# Sheet1.net
KiCad netlist of a schematic drawn in Altium Designer
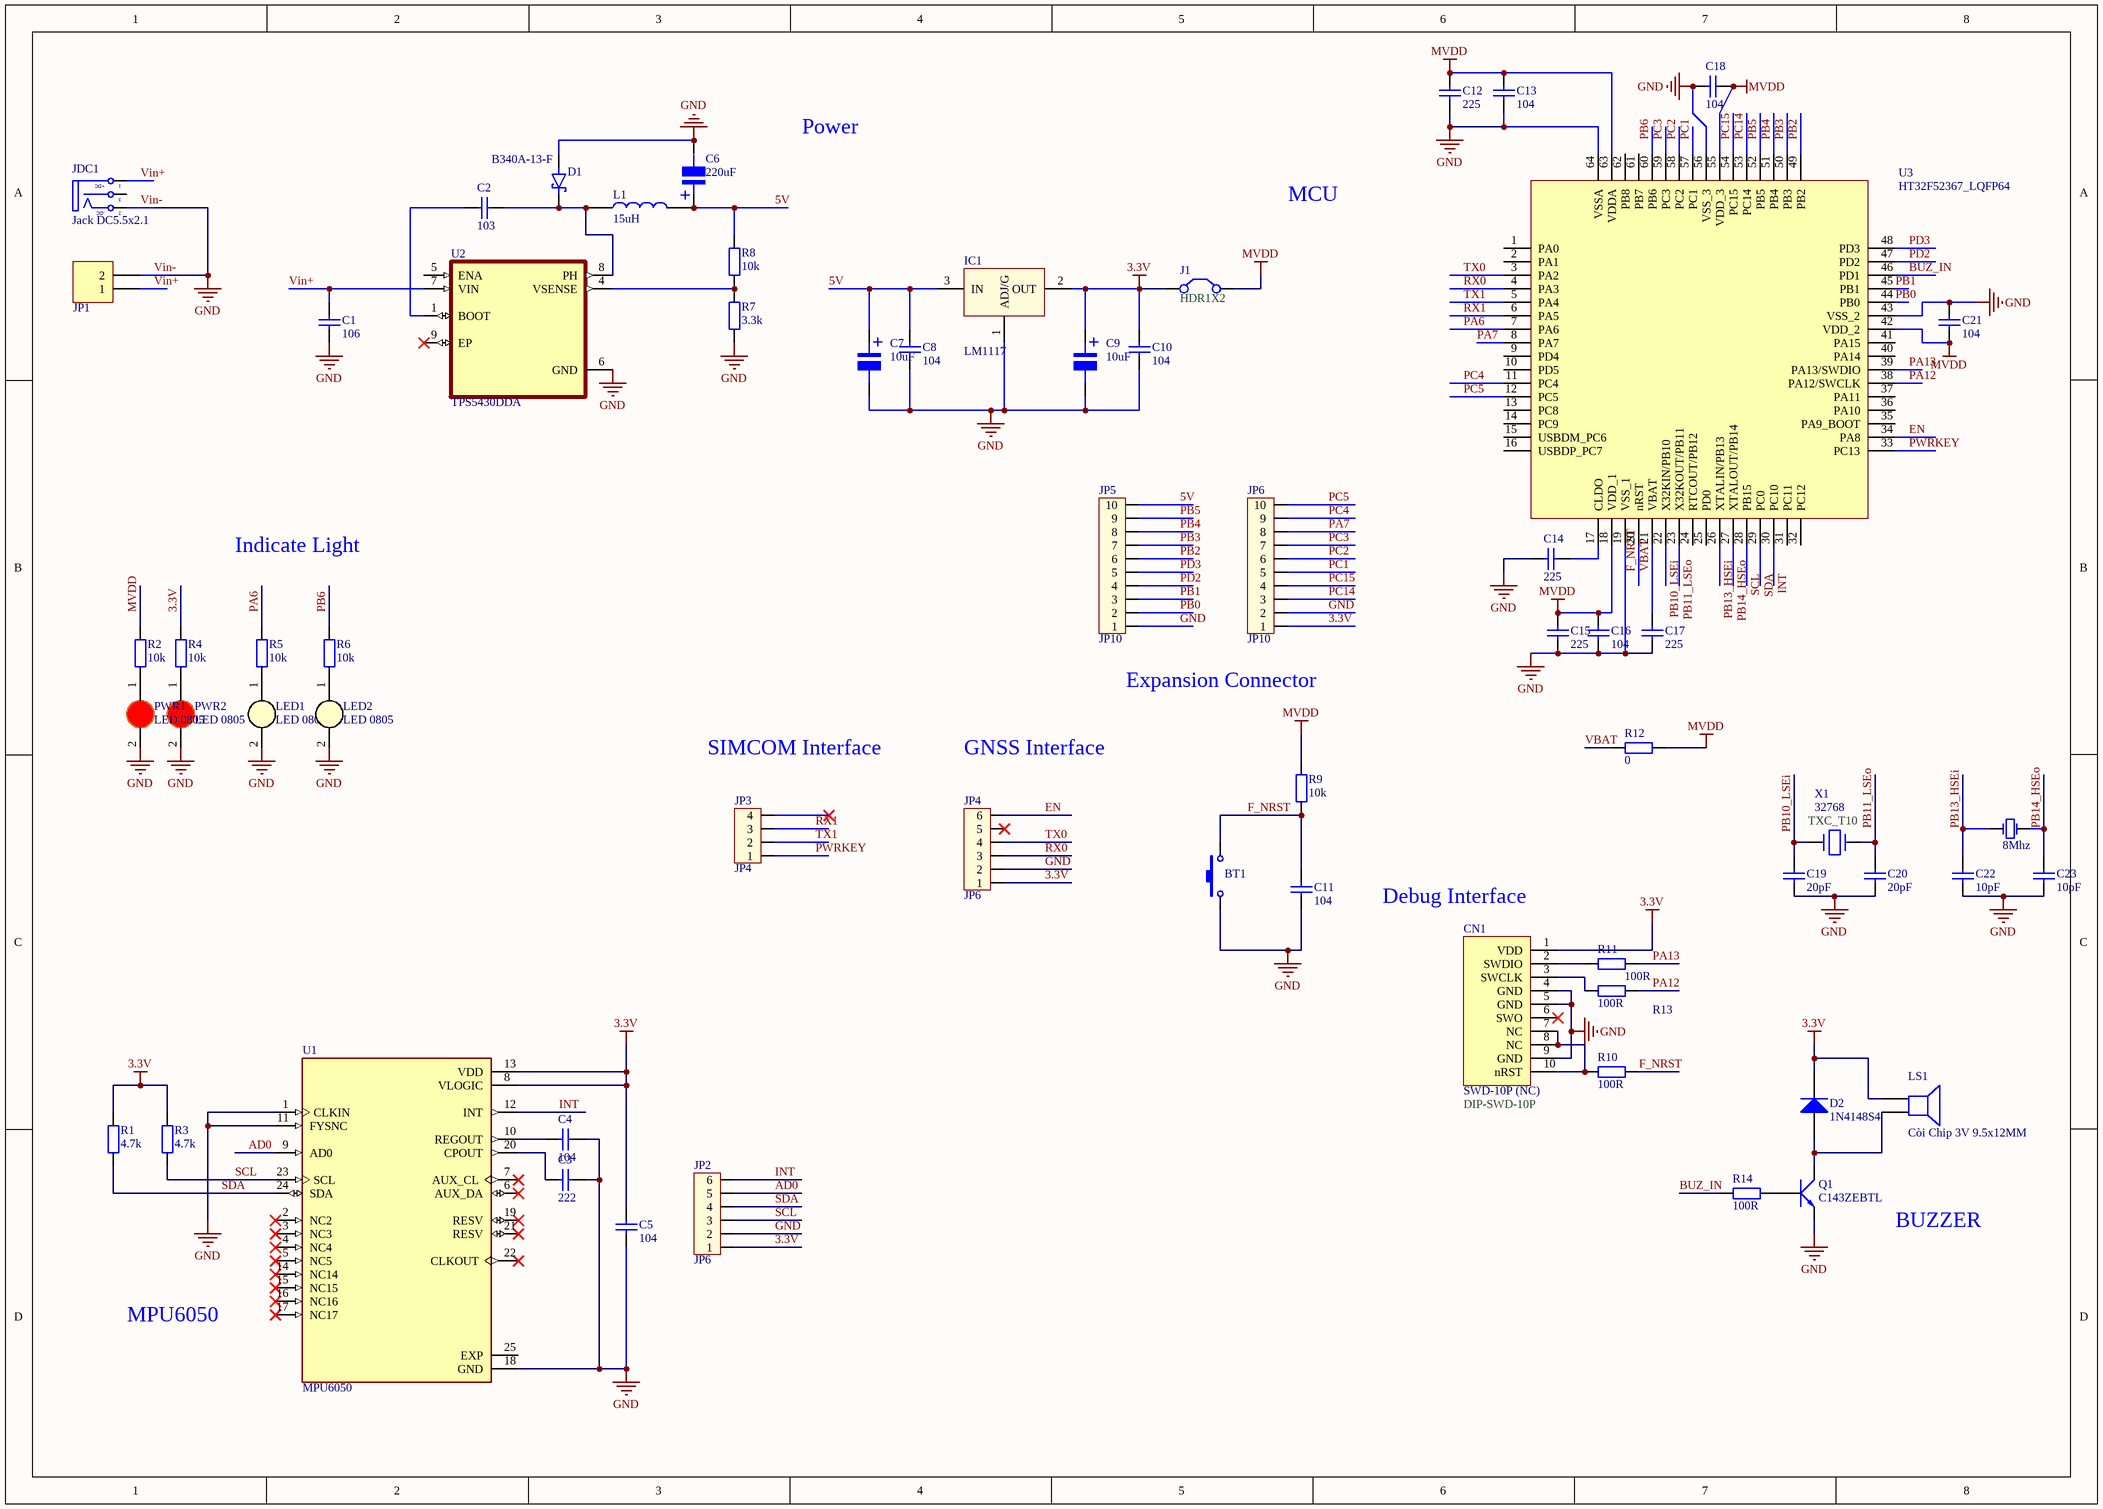
[diagram p0: Sheet1.SchDoc]

(export (version "E")
  (design (tool "Eeschema 10.0.6"))
  (components
    (comp (ref "BT1")
      (value "Nut Nhan 2 Chan SMD 3x6x2.5")
      (footprint "Nut Nhan 2 Chan SMD 3x6x2.5")
      (libsource (lib "Altium_Lib_by_KhueNguyenCreator") (part "Nut Nhan 2 Chan SMD 3x6x2.5"))
    )
    (comp (ref "C1")
      (value "106")
      (footprint "Tu 0805")
      (description "Dán")
      (libsource (lib "THU VIEN SCH") (part "Tu 0805 106 16V 10%"))
    )
    (comp (ref "C2")
      (value "103")
      (footprint "tu 0805")
      (description "Dán")
      (libsource (lib "THU VIEN SCH") (part "Tu 0805 104 50V 10%"))
    )
    (comp (ref "C3")
      (value "222")
      (footprint "tu 0805")
      (description "Dán")
      (libsource (lib "THU VIEN SCH") (part "Tu 0805 222 50V 10%"))
    )
    (comp (ref "C4")
      (value "104")
      (footprint "tu 0603")
      (description "Dán")
      (libsource (lib "THU VIEN SCH") (part "Tu 0603 104 50V 10%"))
    )
    (comp (ref "C5")
      (value "104")
      (footprint "tu 0603")
      (description "Dán")
      (libsource (lib "THU VIEN SCH") (part "Tu 0603 104 50V 10%"))
    )
    (comp (ref "C6")
      (value "220uF")
      (footprint "tu nhom 8 (e)")
      (description "Dán")
      (libsource (lib "THU VIEN SCH") (part "Tu Nhom 220uF 10V"))
    )
    (comp (ref "C7")
      (value "10uF")
      (footprint "tu nhom 4 (b)")
      (description "Dán")
      (libsource (lib "THU VIEN SCH") (part "Tu Nhom 10uF 16V"))
    )
    (comp (ref "C8")
      (value "104")
      (footprint "tu 0805")
      (description "Dán")
      (libsource (lib "THU VIEN SCH") (part "Tu 0805 104 50V 10%"))
    )
    (comp (ref "C9")
      (value "10uF")
      (footprint "tu nhom 4 (b)")
      (description "Dán")
      (libsource (lib "THU VIEN SCH") (part "Tu Nhom 10uF 16V"))
    )
    (comp (ref "C10")
      (value "104")
      (footprint "tu 0805")
      (description "Dán")
      (libsource (lib "THU VIEN SCH") (part "Tu 0805 104 50V 10%"))
    )
    (comp (ref "C11")
      (value "104")
      (footprint "tu 0603")
      (description "Dán")
      (libsource (lib "THU VIEN SCH") (part "Tu 0603 104 50V 10%"))
    )
    (comp (ref "C12")
      (value "225")
      (footprint "tu 0805")
      (description "Dán")
      (libsource (lib "THU VIEN SCH") (part "Tu 0805 225 25V 10%"))
    )
    (comp (ref "C13")
      (value "104")
      (footprint "tu 0603")
      (description "Dán")
      (libsource (lib "THU VIEN SCH") (part "Tu 0603 104 50V 10%"))
    )
    (comp (ref "C14")
      (value "225")
      (footprint "tu 0805")
      (description "Dán")
      (libsource (lib "THU VIEN SCH") (part "Tu 0805 225 25V 10%"))
    )
    (comp (ref "C15")
      (value "225")
      (footprint "tu 0805")
      (description "Dán")
      (libsource (lib "THU VIEN SCH") (part "Tu 0805 225 25V 10%"))
    )
    (comp (ref "C16")
      (value "104")
      (footprint "tu 0603")
      (description "Dán")
      (libsource (lib "THU VIEN SCH") (part "Tu 0603 104 50V 10%"))
    )
    (comp (ref "C17")
      (value "225")
      (footprint "tu 0805")
      (description "Dán")
      (libsource (lib "THU VIEN SCH") (part "Tu 0805 225 25V 10%"))
    )
    (comp (ref "C18")
      (value "104")
      (footprint "tu 0603")
      (description "Dán")
      (libsource (lib "THU VIEN SCH") (part "Tu 0603 104 50V 10%"))
    )
    (comp (ref "C19")
      (value "20pF")
      (footprint "tu 0805")
      (description "Dán")
      (libsource (lib "THU VIEN SCH") (part "Tu 0805 20pF 50V 10%"))
    )
    (comp (ref "C20")
      (value "20pF")
      (footprint "tu 0805")
      (description "Dán")
      (libsource (lib "THU VIEN SCH") (part "Tu 0805 20pF 50V 10%"))
    )
    (comp (ref "C21")
      (value "104")
      (footprint "tu 0603")
      (description "Dán")
      (libsource (lib "THU VIEN SCH") (part "Tu 0603 104 50V 10%"))
    )
    (comp (ref "C22")
      (value "10pF")
      (footprint "tu 0603")
      (description "Dán")
      (libsource (lib "THU VIEN SCH") (part "Tu 0603 104 50V 10%"))
    )
    (comp (ref "C23")
      (value "10pF")
      (footprint "tu 0603")
      (description "Dán")
      (libsource (lib "THU VIEN SCH") (part "Tu 0603 104 50V 10%"))
    )
    (comp (ref "CN1")
      (value "SWD-10P (NC)")
      (footprint "DIP-SWD-10P-2")
      (description "SWD Connector")
      (fields (field (name "PACKAGE") "DIP-SWD-10P"))
      (libsource (lib "HT32F12345_SK") (part "DIP-SWD-10P"))
    )
    (comp (ref "D1")
      (value "B340A-13-F")
      (footprint "DIOM5226X240N")
      (description "Diode Schottky 40V 3A Surface Mount SMA")
      (fields (field (name "MF") "Diodes Inc."))
      (libsource (lib "B340A-13-F") (part "B340A-13-F"))
    )
    (comp (ref "D2")
      (value "1N4148S4")
      (footprint "DIODE SOD-123")
      (description "Dán")
      (libsource (lib "Altium_Lib_by_KhueNguyenCreator") (part "Diode S4"))
    )
    (comp (ref "IC1")
      (value "LM1117")
      (footprint "SOT223-4N")
      (description "Available in 1.8V, 2.5V, 2.85V, 3.3V, 5V, and  Adjustable Versions")
      (libsource (lib "syhaunguyen") (part "LM1117"))
    )
    (comp (ref "J1")
      (value "Jumper")
      (footprint "HDR1X2")
      (description "Jumper Wire")
      (fields (field (name "PACKAGE") "HDR1X2"))
      (libsource (lib "HT32F52367_ESK32-30510") (part "Jumper"))
    )
    (comp (ref "JDC1")
      (value "Jack DC5.5x2.1")
      (footprint "DC-IN")
      (description "Cắm")
      (libsource (lib "THU VIEN SCH") (part "Jac_DC"))
    )
    (comp (ref "JP1")
      (value "Header 2_1")
      (footprint "HED2")
      (description "Header, 2-Pin")
      (fields (field (name "MANUFACTURER") "Generic Components"))
      (libsource (lib "syhaunguyen") (part "Header 2_1"))
    )
    (comp (ref "JP2")
      (value "JP6")
      (footprint "CON6")
      (description "Connector 6")
      (libsource (lib "syhaunguyen") (part "Con6"))
    )
    (comp (ref "JP3")
      (value "JP4")
      (footprint "CON4")
      (description "Connector 4")
      (libsource (lib "syhaunguyen") (part "Con4"))
    )
    (comp (ref "JP4")
      (value "JP6")
      (footprint "CON6")
      (description "Connector 6")
      (libsource (lib "syhaunguyen") (part "Con6"))
    )
    (comp (ref "JP5")
      (value "JP10")
      (footprint "CON10")
      (description "Connector 10")
      (libsource (lib "syhaunguyen") (part "Con10"))
    )
    (comp (ref "JP6")
      (value "JP10")
      (footprint "CON10")
      (description "Connector 10")
      (libsource (lib "syhaunguyen") (part "Con10"))
    )
    (comp (ref "L1")
      (value "15uH")
      (footprint "Cuon Cam 7x7x5")
      (description "Dán")
      (libsource (lib "Cuon Cam") (part "CUON CAM 47uH SMD"))
    )
    (comp (ref "LED1")
      (value "LED 0805")
      (footprint "led 0805")
      (description "Dán")
      (libsource (lib "Altium_Lib_by_KhueNguyenCreator") (part "LED 0805 Trang"))
    )
    (comp (ref "LED2")
      (value "LED 0805")
      (footprint "led 0805")
      (description "Dán")
      (libsource (lib "Altium_Lib_by_KhueNguyenCreator") (part "LED 0805 Trang"))
    )
    (comp (ref "LS1")
      (value "Còi Chip 3V 9.5x12MM")
      (footprint "SPEAKER")
      (description "Cắm")
      (libsource (lib "THU VIEN SCH") (part "Coi Chip 5V"))
    )
    (comp (ref "PWR1")
      (value "LED 0805")
      (footprint "led 0805")
      (description "Dán")
      (libsource (lib "Altium_Lib_by_KhueNguyenCreator") (part "LED 0805 Do"))
    )
    (comp (ref "PWR2")
      (value "LED 0805")
      (footprint "led 0805")
      (description "Dán")
      (libsource (lib "Altium_Lib_by_KhueNguyenCreator") (part "LED 0805 Do"))
    )
    (comp (ref "Q1")
      (value "C143ZEBTL")
      (footprint "SOT23")
      (description "NPN transistor")
      (libsource (lib "Altium_Lib_by_KhueNguyenCreator") (part "C1815 HF SMD"))
    )
    (comp (ref "R1")
      (value "4.7k")
      (footprint "tro smd 0805")
      (description "Dán")
      (libsource (lib "THU VIEN SCH") (part "Tro 0805 5% 4.7k"))
    )
    (comp (ref "R2")
      (value "10k")
      (footprint "TRO SMD 0603")
      (description "Dán")
      (libsource (lib "Altium_Lib_by_KhueNguyenCreator") (part "Tro 0603 1% 10k"))
    )
    (comp (ref "R3")
      (value "4.7k")
      (footprint "tro smd 0805")
      (description "Dán")
      (libsource (lib "THU VIEN SCH") (part "Tro 0805 5% 4.7k"))
    )
    (comp (ref "R4")
      (value "10k")
      (footprint "TRO SMD 0603")
      (description "Dán")
      (libsource (lib "Altium_Lib_by_KhueNguyenCreator") (part "Tro 0603 1% 10k"))
    )
    (comp (ref "R5")
      (value "10k")
      (footprint "TRO SMD 0603")
      (description "Dán")
      (libsource (lib "Altium_Lib_by_KhueNguyenCreator") (part "Tro 0603 1% 10k"))
    )
    (comp (ref "R6")
      (value "10k")
      (footprint "TRO SMD 0603")
      (description "Dán")
      (libsource (lib "Altium_Lib_by_KhueNguyenCreator") (part "Tro 0603 1% 10k"))
    )
    (comp (ref "R7")
      (value "3.3k")
      (footprint "tro smd 0805")
      (description "Dán")
      (libsource (lib "THU VIEN SCH") (part "Tro 0805 1% 3.3k"))
    )
    (comp (ref "R8")
      (value "10k")
      (footprint "tro smd 0805")
      (description "Dán")
      (libsource (lib "THU VIEN SCH") (part "Tro 0805 5% 10k"))
    )
    (comp (ref "R9")
      (value "10k")
      (footprint "tro smd 0603")
      (description "Dán")
      (libsource (lib "THU VIEN SCH") (part "Tro 0603 5% 10k"))
    )
    (comp (ref "R10")
      (value "100R")
      (footprint "tro smd 0805")
      (description "Dán")
      (libsource (lib "THU VIEN SCH") (part "Tro 0805 5% 100R"))
    )
    (comp (ref "R11")
      (value "100R")
      (footprint "tro smd 0805")
      (description "Dán")
      (libsource (lib "THU VIEN SCH") (part "Tro 0805 5% 100R"))
    )
    (comp (ref "R12")
      (value "0")
      (footprint "tro smd 0603")
      (description "Dán")
      (libsource (lib "THU VIEN SCH") (part "Tro 0603 5% 10k"))
    )
    (comp (ref "R13")
      (value "100R")
      (footprint "tro smd 0805")
      (description "Dán")
      (libsource (lib "THU VIEN SCH") (part "Tro 0805 5% 100R"))
    )
    (comp (ref "R14")
      (value "100R")
      (footprint "tro smd 0603")
      (description "Dán")
      (libsource (lib "THU VIEN SCH") (part "Tro 0603 5% 100R"))
    )
    (comp (ref "U1")
      (value "MPU6050")
      (footprint "IC_MPU6050")
      (description "Accelerometer, Gyroscope, 6 Axis Sensor IÂ²C Output")
      (fields (field (name "MF") "TDK InvenSense"))
      (libsource (lib "MPU6050") (part "MPU6050"))
    )
    (comp (ref "U2")
      (value "TPS5430DDA")
      (footprint "VREG_LM5017MR/NOPB")
      (description "5.5Vè‡³36Vè¾“å…¥ï¼Œ3Aï¼Œ500kHzé™åŽ‹è½¬æ¢å™¨")
      (fields (field (name "MF") "Texas Instruments"))
      (libsource (lib "TPS5430DDA") (part "TPS5430DDA"))
    )
    (comp (ref "U3")
      (value "HT32F52367_LQFP64")
      (footprint "HT_LQFP64")
      (libsource (lib "Holtek") (part "HT32F52367_LQFP64"))
    )
    (comp (ref "X1")
      (value "32768")
      (footprint "TXC_T10")
      (description "SMD XTAL")
      (fields (field (name "PACKAGE") "TXC_T10"))
      (libsource (lib "HT32F12345_SK") (part "XTAL_TXC-T10"))
    )
    (comp (ref "Y1")
      (value "8Mhz")
      (footprint "XT2")
      (description "Cắm")
      (libsource (lib "THU VIEN SCH") (part "Thach Anh 8Mhz DIP"))
    )
  )
  (nets
    (net (code "1") (name "/5V") (class "Default")
      (node (ref "C6") (pin "1") (pinfunction "1_1") (pintype "passive"))
      (node (ref "C7") (pin "1") (pinfunction "1_1") (pintype "passive"))
      (node (ref "C8") (pin "1") (pinfunction "1_1") (pintype "passive"))
      (node (ref "IC1") (pin "3") (pinfunction "IN_3") (pintype "passive"))
      (node (ref "JP5") (pin "10") (pinfunction "10_10") (pintype "passive"))
      (node (ref "L1") (pin "2") (pinfunction "2_2") (pintype "passive"))
      (node (ref "R8") (pin "2") (pinfunction "2_2") (pintype "passive"))
    )
    (net (code "2") (name "/AD0") (class "Default")
      (node (ref "JP2") (pin "5") (pinfunction "5_5") (pintype "passive"))
      (node (ref "U1") (pin "9") (pinfunction "AD0_9") (pintype "input"))
    )
    (net (code "4") (name "/BUZ_IN") (class "Default")
      (node (ref "R14") (pin "1") (pinfunction "1_1") (pintype "passive"))
      (node (ref "U3") (pin "46") (pinfunction "PD1_46") (pintype "passive"))
    )
    (net (code "6") (name "/EN") (class "Default")
      (node (ref "JP4") (pin "6") (pinfunction "6_6") (pintype "passive"))
      (node (ref "U3") (pin "34") (pinfunction "PA8_34") (pintype "passive"))
    )
    (net (code "8") (name "/F_NRST") (class "Default")
      (node (ref "BT1") (pin "2") (pinfunction "2_2") (pintype "passive"))
      (node (ref "C11") (pin "1") (pinfunction "1_1") (pintype "passive"))
      (node (ref "R10") (pin "2") (pinfunction "2_2") (pintype "passive"))
      (node (ref "R9") (pin "1") (pinfunction "1_1") (pintype "passive"))
      (node (ref "U3") (pin "20") (pinfunction "nRST_20") (pintype "passive"))
    )
    (net (code "10") (name "/INT") (class "Default")
      (node (ref "JP2") (pin "6") (pinfunction "6_6") (pintype "passive"))
      (node (ref "U1") (pin "12") (pinfunction "INT_12") (pintype "output"))
      (node (ref "U3") (pin "30") (pinfunction "PC10_30") (pintype "passive"))
    )
    (net (code "14") (name "/PA6") (class "Default")
      (node (ref "R5") (pin "2") (pinfunction "2_2") (pintype "passive"))
      (node (ref "U3") (pin "7") (pinfunction "PA6_7") (pintype "passive"))
    )
    (net (code "15") (name "/PA7") (class "Default")
      (node (ref "JP6") (pin "8") (pinfunction "8_8") (pintype "passive"))
      (node (ref "U3") (pin "8") (pinfunction "PA7_8") (pintype "passive"))
    )
    (net (code "16") (name "/PA12") (class "Default")
      (node (ref "R13") (pin "2") (pinfunction "2_2") (pintype "passive"))
      (node (ref "U3") (pin "38") (pinfunction "PA12/SWCLK_38") (pintype "passive"))
    )
    (net (code "17") (name "/PA13") (class "Default")
      (node (ref "R11") (pin "2") (pinfunction "2_2") (pintype "passive"))
      (node (ref "U3") (pin "39") (pinfunction "PA13/SWDIO_39") (pintype "passive"))
    )
    (net (code "18") (name "/PB0") (class "Default")
      (node (ref "JP5") (pin "2") (pinfunction "2_2") (pintype "passive"))
      (node (ref "U3") (pin "44") (pinfunction "PB0_44") (pintype "passive"))
    )
    (net (code "19") (name "/PB1") (class "Default")
      (node (ref "JP5") (pin "3") (pinfunction "3_3") (pintype "passive"))
      (node (ref "U3") (pin "45") (pinfunction "PB1_45") (pintype "passive"))
    )
    (net (code "20") (name "/PB2") (class "Default")
      (node (ref "JP5") (pin "6") (pinfunction "6_6") (pintype "passive"))
      (node (ref "U3") (pin "49") (pinfunction "PB2_49") (pintype "passive"))
    )
    (net (code "21") (name "/PB3") (class "Default")
      (node (ref "JP5") (pin "7") (pinfunction "7_7") (pintype "passive"))
      (node (ref "U3") (pin "50") (pinfunction "PB3_50") (pintype "passive"))
    )
    (net (code "22") (name "/PB4") (class "Default")
      (node (ref "JP5") (pin "8") (pinfunction "8_8") (pintype "passive"))
      (node (ref "U3") (pin "51") (pinfunction "PB4_51") (pintype "passive"))
    )
    (net (code "23") (name "/PB5") (class "Default")
      (node (ref "JP5") (pin "9") (pinfunction "9_9") (pintype "passive"))
      (node (ref "U3") (pin "52") (pinfunction "PB5_52") (pintype "passive"))
    )
    (net (code "24") (name "/PB6") (class "Default")
      (node (ref "R6") (pin "2") (pinfunction "2_2") (pintype "passive"))
      (node (ref "U3") (pin "60") (pinfunction "PB6_60") (pintype "passive"))
    )
    (net (code "25") (name "/PB10_LSEi") (class "Default")
      (node (ref "C19") (pin "1") (pinfunction "1_1") (pintype "passive"))
      (node (ref "U3") (pin "22") (pinfunction "X32KIN/PB10_22") (pintype "passive"))
      (node (ref "X1") (pin "1") (pinfunction "1_1") (pintype "passive"))
    )
    (net (code "26") (name "/PB11_LSEo") (class "Default")
      (node (ref "C20") (pin "1") (pinfunction "1_1") (pintype "passive"))
      (node (ref "U3") (pin "23") (pinfunction "X32KOUT/PB11_23") (pintype "passive"))
      (node (ref "X1") (pin "2") (pinfunction "2_2") (pintype "passive"))
    )
    (net (code "27") (name "/PB13_HSEi") (class "Default")
      (node (ref "C22") (pin "1") (pinfunction "1_1") (pintype "passive"))
      (node (ref "U3") (pin "26") (pinfunction "XTALIN/PB13_26") (pintype "passive"))
      (node (ref "Y1") (pin "1") (pinfunction "OSC1_1") (pintype "passive"))
    )
    (net (code "28") (name "/PB14_HSEo") (class "Default")
      (node (ref "C23") (pin "1") (pinfunction "1_1") (pintype "passive"))
      (node (ref "U3") (pin "27") (pinfunction "XTALOUT/PB14_27") (pintype "passive"))
      (node (ref "Y1") (pin "2") (pinfunction "OSC2_2") (pintype "passive"))
    )
    (net (code "29") (name "/PC1") (class "Default")
      (node (ref "JP6") (pin "5") (pinfunction "5_5") (pintype "passive"))
      (node (ref "U3") (pin "57") (pinfunction "PC1_57") (pintype "passive"))
    )
    (net (code "30") (name "/PC2") (class "Default")
      (node (ref "JP6") (pin "6") (pinfunction "6_6") (pintype "passive"))
      (node (ref "U3") (pin "58") (pinfunction "PC2_58") (pintype "passive"))
    )
    (net (code "31") (name "/PC3") (class "Default")
      (node (ref "JP6") (pin "7") (pinfunction "7_7") (pintype "passive"))
      (node (ref "U3") (pin "59") (pinfunction "PC3_59") (pintype "passive"))
    )
    (net (code "32") (name "/PC4") (class "Default")
      (node (ref "JP6") (pin "9") (pinfunction "9_9") (pintype "passive"))
      (node (ref "U3") (pin "11") (pinfunction "PC4_11") (pintype "passive"))
    )
    (net (code "33") (name "/PC5") (class "Default")
      (node (ref "JP6") (pin "10") (pinfunction "10_10") (pintype "passive"))
      (node (ref "U3") (pin "12") (pinfunction "PC5_12") (pintype "passive"))
    )
    (net (code "34") (name "/PC14") (class "Default")
      (node (ref "JP6") (pin "3") (pinfunction "3_3") (pintype "passive"))
      (node (ref "U3") (pin "53") (pinfunction "PC14_53") (pintype "passive"))
    )
    (net (code "35") (name "/PC15") (class "Default")
      (node (ref "JP6") (pin "4") (pinfunction "4_4") (pintype "passive"))
      (node (ref "U3") (pin "54") (pinfunction "PC15_54") (pintype "passive"))
    )
    (net (code "36") (name "/PD2") (class "Default")
      (node (ref "JP5") (pin "4") (pinfunction "4_4") (pintype "passive"))
      (node (ref "U3") (pin "47") (pinfunction "PD2_47") (pintype "passive"))
    )
    (net (code "37") (name "/PD3") (class "Default")
      (node (ref "JP5") (pin "5") (pinfunction "5_5") (pintype "passive"))
      (node (ref "U3") (pin "48") (pinfunction "PD3_48") (pintype "passive"))
    )
    (net (code "38") (name "/PWRKEY") (class "Default")
      (node (ref "JP3") (pin "1") (pinfunction "1_1") (pintype "passive"))
      (node (ref "U3") (pin "33") (pinfunction "PC13_33") (pintype "passive"))
    )
    (net (code "40") (name "/RX0") (class "Default")
      (node (ref "JP4") (pin "3") (pinfunction "3_3") (pintype "passive"))
      (node (ref "U3") (pin "4") (pinfunction "PA3_4") (pintype "passive"))
    )
    (net (code "41") (name "/RX1") (class "Default")
      (node (ref "JP3") (pin "3") (pinfunction "3_3") (pintype "passive"))
      (node (ref "U3") (pin "6") (pinfunction "PA5_6") (pintype "passive"))
    )
    (net (code "42") (name "/SCL") (class "Default")
      (node (ref "JP2") (pin "3") (pinfunction "3_3") (pintype "passive"))
      (node (ref "R3") (pin "1") (pinfunction "1_1") (pintype "passive"))
      (node (ref "U1") (pin "23") (pinfunction "SCL_23") (pintype "input"))
      (node (ref "U3") (pin "28") (pinfunction "PB15_28") (pintype "passive"))
    )
    (net (code "43") (name "/SDA") (class "Default")
      (node (ref "JP2") (pin "4") (pinfunction "4_4") (pintype "passive"))
      (node (ref "R1") (pin "1") (pinfunction "1_1") (pintype "passive"))
      (node (ref "U1") (pin "24") (pinfunction "SDA_24") (pintype "bidirectional"))
      (node (ref "U3") (pin "29") (pinfunction "PC0_29") (pintype "passive"))
    )
    (net (code "45") (name "/TX0") (class "Default")
      (node (ref "JP4") (pin "4") (pinfunction "4_4") (pintype "passive"))
      (node (ref "U3") (pin "3") (pinfunction "PA2_3") (pintype "passive"))
    )
    (net (code "46") (name "/TX1") (class "Default")
      (node (ref "JP3") (pin "2") (pinfunction "2_2") (pintype "passive"))
      (node (ref "U3") (pin "5") (pinfunction "PA4_5") (pintype "passive"))
    )
    (net (code "47") (name "/VBAT") (class "Default")
      (node (ref "C17") (pin "2") (pinfunction "2_2") (pintype "passive"))
      (node (ref "R12") (pin "2") (pinfunction "2_2") (pintype "passive"))
      (node (ref "U3") (pin "21") (pinfunction "VBAT_21") (pintype "passive"))
    )
    (net (code "48") (name "/Vin+") (class "Default")
      (node (ref "C1") (pin "1") (pinfunction "1_1") (pintype "passive"))
      (node (ref "JDC1") (pin "1") (pinfunction "T_1") (pintype "passive"))
      (node (ref "JP1") (pin "1") (pinfunction "1_1") (pintype "passive"))
      (node (ref "U2") (pin "7") (pinfunction "VIN_7") (pintype "input"))
    )
    (net (code "49") (name "3.3V") (class "Default")
      (node (ref "C10") (pin "1") (pinfunction "1_1") (pintype "passive"))
      (node (ref "C5") (pin "1") (pinfunction "1_1") (pintype "passive"))
      (node (ref "C9") (pin "1") (pinfunction "1_1") (pintype "passive"))
      (node (ref "CN1") (pin "1") (pinfunction "VDD_1") (pintype "passive"))
      (node (ref "D2") (pin "2") (pinfunction "K_2") (pintype "passive"))
      (node (ref "IC1") (pin "2") (pinfunction "OUT_2") (pintype "passive"))
      (node (ref "J1") (pin "1") (pinfunction "C1_1") (pintype "passive"))
      (node (ref "JP2") (pin "1") (pinfunction "1_1") (pintype "passive"))
      (node (ref "JP4") (pin "1") (pinfunction "1_1") (pintype "passive"))
      (node (ref "JP6") (pin "1") (pinfunction "1_1") (pintype "passive"))
      (node (ref "LS1") (pin "1") (pinfunction "1_1") (pintype "passive"))
      (node (ref "R1") (pin "2") (pinfunction "2_2") (pintype "passive"))
      (node (ref "R3") (pin "2") (pinfunction "2_2") (pintype "passive"))
      (node (ref "R4") (pin "2") (pinfunction "2_2") (pintype "passive"))
      (node (ref "U1") (pin "13") (pinfunction "VDD_13") (pintype "power_in"))
      (node (ref "U1") (pin "8") (pinfunction "VLOGIC_8") (pintype "power_in"))
    )
    (net (code "50") (name "GND") (class "Default")
      (node (ref "BT1") (pin "1") (pinfunction "1_1") (pintype "passive"))
      (node (ref "C1") (pin "2") (pinfunction "2_2") (pintype "passive"))
      (node (ref "C10") (pin "2") (pinfunction "2_2") (pintype "passive"))
      (node (ref "C11") (pin "2") (pinfunction "2_2") (pintype "passive"))
      (node (ref "C12") (pin "1") (pinfunction "1_1") (pintype "passive"))
      (node (ref "C13") (pin "1") (pinfunction "1_1") (pintype "passive"))
      (node (ref "C14") (pin "1") (pinfunction "1_1") (pintype "passive"))
      (node (ref "C15") (pin "2") (pinfunction "2_2") (pintype "passive"))
      (node (ref "C16") (pin "2") (pinfunction "2_2") (pintype "passive"))
      (node (ref "C17") (pin "1") (pinfunction "1_1") (pintype "passive"))
      (node (ref "C18") (pin "2") (pinfunction "2_2") (pintype "passive"))
      (node (ref "C19") (pin "2") (pinfunction "2_2") (pintype "passive"))
      (node (ref "C20") (pin "2") (pinfunction "2_2") (pintype "passive"))
      (node (ref "C21") (pin "2") (pinfunction "2_2") (pintype "passive"))
      (node (ref "C22") (pin "2") (pinfunction "2_2") (pintype "passive"))
      (node (ref "C23") (pin "2") (pinfunction "2_2") (pintype "passive"))
      (node (ref "C3") (pin "1") (pinfunction "1_1") (pintype "passive"))
      (node (ref "C4") (pin "2") (pinfunction "2_2") (pintype "passive"))
      (node (ref "C5") (pin "2") (pinfunction "2_2") (pintype "passive"))
      (node (ref "C6") (pin "2") (pinfunction "2_2") (pintype "passive"))
      (node (ref "C7") (pin "2") (pinfunction "2_2") (pintype "passive"))
      (node (ref "C8") (pin "2") (pinfunction "2_2") (pintype "passive"))
      (node (ref "C9") (pin "2") (pinfunction "2_2") (pintype "passive"))
      (node (ref "CN1") (pin "4") (pinfunction "GND_4") (pintype "passive"))
      (node (ref "CN1") (pin "5") (pinfunction "GND_5") (pintype "passive"))
      (node (ref "CN1") (pin "9") (pinfunction "GND_9") (pintype "passive"))
      (node (ref "D1") (pin "A") (pinfunction "A_A") (pintype "passive"))
      (node (ref "IC1") (pin "1") (pinfunction "ADJ/G_1") (pintype "passive"))
      (node (ref "JDC1") (pin "2") (pinfunction "TN_2") (pintype "passive"))
      (node (ref "JP1") (pin "2") (pinfunction "2_2") (pintype "passive"))
      (node (ref "JP2") (pin "2") (pinfunction "2_2") (pintype "passive"))
      (node (ref "JP4") (pin "2") (pinfunction "2_2") (pintype "passive"))
      (node (ref "JP5") (pin "1") (pinfunction "1_1") (pintype "passive"))
      (node (ref "JP6") (pin "2") (pinfunction "2_2") (pintype "passive"))
      (node (ref "LED1") (pin "2") (pinfunction "K_2") (pintype "passive"))
      (node (ref "LED2") (pin "2") (pinfunction "K_2") (pintype "passive"))
      (node (ref "PWR1") (pin "2") (pinfunction "K_2") (pintype "passive"))
      (node (ref "PWR2") (pin "2") (pinfunction "K_2") (pintype "passive"))
      (node (ref "Q1") (pin "2") (pinfunction "E_2") (pintype "passive"))
      (node (ref "R7") (pin "1") (pinfunction "1_1") (pintype "passive"))
      (node (ref "U1") (pin "1") (pinfunction "CLKIN_1") (pintype "input"))
      (node (ref "U1") (pin "11") (pinfunction "FYSNC_11") (pintype "input"))
      (node (ref "U1") (pin "18") (pinfunction "GND_18") (pintype "power_in"))
      (node (ref "U2") (pin "6") (pinfunction "GND_6") (pintype "power_in"))
      (node (ref "U3") (pin "19") (pinfunction "VSS_1_19") (pintype "passive"))
      (node (ref "U3") (pin "43") (pinfunction "VSS_2_43") (pintype "passive"))
      (node (ref "U3") (pin "56") (pinfunction "VSS_3_56") (pintype "passive"))
      (node (ref "U3") (pin "64") (pinfunction "VSSA_64") (pintype "passive"))
    )
    (net (code "51") (name "MVDD") (class "Default")
      (node (ref "C12") (pin "2") (pinfunction "2_2") (pintype "passive"))
      (node (ref "C13") (pin "2") (pinfunction "2_2") (pintype "passive"))
      (node (ref "C15") (pin "1") (pinfunction "1_1") (pintype "passive"))
      (node (ref "C16") (pin "1") (pinfunction "1_1") (pintype "passive"))
      (node (ref "C18") (pin "1") (pinfunction "1_1") (pintype "passive"))
      (node (ref "C21") (pin "1") (pinfunction "1_1") (pintype "passive"))
      (node (ref "J1") (pin "2") (pinfunction "C2_2") (pintype "passive"))
      (node (ref "R12") (pin "1") (pinfunction "1_1") (pintype "passive"))
      (node (ref "R2") (pin "2") (pinfunction "2_2") (pintype "passive"))
      (node (ref "R9") (pin "2") (pinfunction "2_2") (pintype "passive"))
      (node (ref "U3") (pin "18") (pinfunction "VDD_1_18") (pintype "passive"))
      (node (ref "U3") (pin "42") (pinfunction "VDD_2_42") (pintype "passive"))
      (node (ref "U3") (pin "55") (pinfunction "VDD_3_55") (pintype "passive"))
      (node (ref "U3") (pin "63") (pinfunction "VDDA_63") (pintype "passive"))
    )
    (net (code "52") (name "Net-(CN1-SWCLK)") (class "Default")
      (node (ref "CN1") (pin "3") (pinfunction "SWCLK_3") (pintype "passive"))
      (node (ref "R13") (pin "1") (pinfunction "1_1") (pintype "passive"))
    )
    (net (code "53") (name "Net-(CN1-SWDIO)") (class "Default")
      (node (ref "CN1") (pin "2") (pinfunction "SWDIO_2") (pintype "passive"))
      (node (ref "R11") (pin "1") (pinfunction "1_1") (pintype "passive"))
    )
    (net (code "54") (name "Net-(CN1-nRST)") (class "Default")
      (node (ref "CN1") (pin "10") (pinfunction "nRST_10") (pintype "passive"))
      (node (ref "CN1") (pin "7") (pinfunction "NC_7") (pintype "passive"))
      (node (ref "CN1") (pin "8") (pinfunction "NC_8") (pintype "passive"))
      (node (ref "R10") (pin "1") (pinfunction "1_1") (pintype "passive"))
    )
    (net (code "55") (name "Net-(D2-A)") (class "Default")
      (node (ref "D2") (pin "1") (pinfunction "A_1") (pintype "passive"))
      (node (ref "LS1") (pin "2") (pinfunction "2_2") (pintype "passive"))
      (node (ref "Q1") (pin "3") (pinfunction "C_3") (pintype "passive"))
    )
    (net (code "56") (name "Net-(LED1-A)") (class "Default")
      (node (ref "LED1") (pin "1") (pinfunction "A_1") (pintype "passive"))
      (node (ref "R5") (pin "1") (pinfunction "1_1") (pintype "passive"))
    )
    (net (code "57") (name "Net-(LED2-A)") (class "Default")
      (node (ref "LED2") (pin "1") (pinfunction "A_1") (pintype "passive"))
      (node (ref "R6") (pin "1") (pinfunction "1_1") (pintype "passive"))
    )
    (net (code "58") (name "Net-(PWR1-A)") (class "Default")
      (node (ref "PWR1") (pin "1") (pinfunction "A_1") (pintype "passive"))
      (node (ref "R2") (pin "1") (pinfunction "1_1") (pintype "passive"))
    )
    (net (code "59") (name "Net-(PWR2-A)") (class "Default")
      (node (ref "PWR2") (pin "1") (pinfunction "A_1") (pintype "passive"))
      (node (ref "R4") (pin "1") (pinfunction "1_1") (pintype "passive"))
    )
    (net (code "60") (name "Net-(Q1-B)") (class "Default")
      (node (ref "Q1") (pin "1") (pinfunction "B_1") (pintype "passive"))
      (node (ref "R14") (pin "2") (pinfunction "2_2") (pintype "passive"))
    )
    (net (code "61") (name "Net-(U1-CPOUT)") (class "Default")
      (node (ref "C3") (pin "2") (pinfunction "2_2") (pintype "passive"))
      (node (ref "U1") (pin "20") (pinfunction "CPOUT_20") (pintype "output"))
    )
    (net (code "62") (name "Net-(U1-REGOUT)") (class "Default")
      (node (ref "C4") (pin "1") (pinfunction "1_1") (pintype "passive"))
      (node (ref "U1") (pin "10") (pinfunction "REGOUT_10") (pintype "output"))
    )
    (net (code "63") (name "Net-(U2-BOOT)") (class "Default")
      (node (ref "C2") (pin "2") (pinfunction "2_2") (pintype "passive"))
      (node (ref "U2") (pin "1") (pinfunction "BOOT_1") (pintype "bidirectional"))
    )
    (net (code "64") (name "Net-(U2-PH)") (class "Default")
      (node (ref "C2") (pin "1") (pinfunction "1_1") (pintype "passive"))
      (node (ref "D1") (pin "C") (pinfunction "C_C") (pintype "passive"))
      (node (ref "L1") (pin "1") (pinfunction "1_1") (pintype "passive"))
      (node (ref "U2") (pin "8") (pinfunction "PH_8") (pintype "output"))
    )
    (net (code "65") (name "Net-(U2-VSENSE)") (class "Default")
      (node (ref "R7") (pin "2") (pinfunction "2_2") (pintype "passive"))
      (node (ref "R8") (pin "1") (pinfunction "1_1") (pintype "passive"))
      (node (ref "U2") (pin "4") (pinfunction "VSENSE_4") (pintype "output"))
    )
    (net (code "66") (name "Net-(U3-CLDO)") (class "Default")
      (node (ref "C14") (pin "2") (pinfunction "2_2") (pintype "passive"))
      (node (ref "U3") (pin "17") (pinfunction "CLDO_17") (pintype "passive"))
    )
    (net (code "67") (name "unconnected-(CN1-SWO-Pad6)") (class "Default")
      (node (ref "CN1") (pin "6") (pinfunction "SWO_6") (pintype "passive+no_connect"))
    )
    (net (code "68") (name "unconnected-(JDC1-S-Pad3)") (class "Default")
      (node (ref "JDC1") (pin "3") (pinfunction "S_3") (pintype "power_in"))
    )
    (net (code "69") (name "unconnected-(JP3-Pad4)") (class "Default")
      (node (ref "JP3") (pin "4") (pinfunction "4_4") (pintype "passive+no_connect"))
    )
    (net (code "70") (name "unconnected-(JP4-Pad5)") (class "Default")
      (node (ref "JP4") (pin "5") (pinfunction "5_5") (pintype "passive+no_connect"))
    )
    (net (code "71") (name "unconnected-(U1-AUX_CL-Pad7)") (class "Default")
      (node (ref "U1") (pin "7") (pinfunction "AUX_CL_7") (pintype "output+no_connect"))
    )
    (net (code "72") (name "unconnected-(U1-AUX_DA-Pad6)") (class "Default")
      (node (ref "U1") (pin "6") (pinfunction "AUX_DA_6") (pintype "bidirectional+no_connect"))
    )
    (net (code "73") (name "unconnected-(U1-CLKOUT-Pad22)") (class "Default")
      (node (ref "U1") (pin "22") (pinfunction "CLKOUT_22") (pintype "output+no_connect"))
    )
    (net (code "74") (name "unconnected-(U1-EXP-Pad25)") (class "Default")
      (node (ref "U1") (pin "25") (pinfunction "EXP_25") (pintype "power_in"))
    )
    (net (code "75") (name "unconnected-(U1-NC2-Pad2)") (class "Default")
      (node (ref "U1") (pin "2") (pinfunction "NC2_2") (pintype "input+no_connect"))
    )
    (net (code "76") (name "unconnected-(U1-NC3-Pad3)") (class "Default")
      (node (ref "U1") (pin "3") (pinfunction "NC3_3") (pintype "input+no_connect"))
    )
    (net (code "77") (name "unconnected-(U1-NC4-Pad4)") (class "Default")
      (node (ref "U1") (pin "4") (pinfunction "NC4_4") (pintype "input+no_connect"))
    )
    (net (code "78") (name "unconnected-(U1-NC5-Pad5)") (class "Default")
      (node (ref "U1") (pin "5") (pinfunction "NC5_5") (pintype "input+no_connect"))
    )
    (net (code "79") (name "unconnected-(U1-NC14-Pad14)") (class "Default")
      (node (ref "U1") (pin "14") (pinfunction "NC14_14") (pintype "input+no_connect"))
    )
    (net (code "80") (name "unconnected-(U1-NC15-Pad15)") (class "Default")
      (node (ref "U1") (pin "15") (pinfunction "NC15_15") (pintype "input+no_connect"))
    )
    (net (code "81") (name "unconnected-(U1-NC16-Pad16)") (class "Default")
      (node (ref "U1") (pin "16") (pinfunction "NC16_16") (pintype "input+no_connect"))
    )
    (net (code "82") (name "unconnected-(U1-NC17-Pad17)") (class "Default")
      (node (ref "U1") (pin "17") (pinfunction "NC17_17") (pintype "input+no_connect"))
    )
    (net (code "83") (name "unconnected-(U1-RESV-Pad19)") (class "Default")
      (node (ref "U1") (pin "19") (pinfunction "RESV_19") (pintype "bidirectional+no_connect"))
    )
    (net (code "84") (name "unconnected-(U1-RESV-Pad21)") (class "Default")
      (node (ref "U1") (pin "21") (pinfunction "RESV_21") (pintype "bidirectional+no_connect"))
    )
    (net (code "85") (name "unconnected-(U2-ENA-Pad5)") (class "Default")
      (node (ref "U2") (pin "5") (pinfunction "ENA_5") (pintype "input"))
    )
    (net (code "86") (name "unconnected-(U2-EP-Pad9)") (class "Default")
      (node (ref "U2") (pin "9") (pinfunction "EP_9") (pintype "bidirectional+no_connect"))
    )
    (net (code "87") (name "unconnected-(U3-PA0-Pad1)") (class "Default")
      (node (ref "U3") (pin "1") (pinfunction "PA0_1") (pintype "passive"))
    )
    (net (code "88") (name "unconnected-(U3-PA1-Pad2)") (class "Default")
      (node (ref "U3") (pin "2") (pinfunction "PA1_2") (pintype "passive"))
    )
    (net (code "89") (name "unconnected-(U3-PA9_BOOT-Pad35)") (class "Default")
      (node (ref "U3") (pin "35") (pinfunction "PA9_BOOT_35") (pintype "passive"))
    )
    (net (code "90") (name "unconnected-(U3-PA10-Pad36)") (class "Default")
      (node (ref "U3") (pin "36") (pinfunction "PA10_36") (pintype "passive"))
    )
    (net (code "91") (name "unconnected-(U3-PA11-Pad37)") (class "Default")
      (node (ref "U3") (pin "37") (pinfunction "PA11_37") (pintype "passive"))
    )
    (net (code "92") (name "unconnected-(U3-PA14-Pad40)") (class "Default")
      (node (ref "U3") (pin "40") (pinfunction "PA14_40") (pintype "passive"))
    )
    (net (code "93") (name "unconnected-(U3-PA15-Pad41)") (class "Default")
      (node (ref "U3") (pin "41") (pinfunction "PA15_41") (pintype "passive"))
    )
    (net (code "94") (name "unconnected-(U3-PB7-Pad61)") (class "Default")
      (node (ref "U3") (pin "61") (pinfunction "PB7_61") (pintype "passive"))
    )
    (net (code "95") (name "unconnected-(U3-PB8-Pad62)") (class "Default")
      (node (ref "U3") (pin "62") (pinfunction "PB8_62") (pintype "passive"))
    )
    (net (code "96") (name "unconnected-(U3-PC8-Pad13)") (class "Default")
      (node (ref "U3") (pin "13") (pinfunction "PC8_13") (pintype "passive"))
    )
    (net (code "97") (name "unconnected-(U3-PC9-Pad14)") (class "Default")
      (node (ref "U3") (pin "14") (pinfunction "PC9_14") (pintype "passive"))
    )
    (net (code "98") (name "unconnected-(U3-PC11-Pad31)") (class "Default")
      (node (ref "U3") (pin "31") (pinfunction "PC11_31") (pintype "passive"))
    )
    (net (code "99") (name "unconnected-(U3-PC12-Pad32)") (class "Default")
      (node (ref "U3") (pin "32") (pinfunction "PC12_32") (pintype "passive"))
    )
    (net (code "100") (name "unconnected-(U3-PD0-Pad25)") (class "Default")
      (node (ref "U3") (pin "25") (pinfunction "PD0_25") (pintype "passive"))
    )
    (net (code "101") (name "unconnected-(U3-PD4-Pad9)") (class "Default")
      (node (ref "U3") (pin "9") (pinfunction "PD4_9") (pintype "passive"))
    )
    (net (code "102") (name "unconnected-(U3-PD5-Pad10)") (class "Default")
      (node (ref "U3") (pin "10") (pinfunction "PD5_10") (pintype "passive"))
    )
    (net (code "103") (name "unconnected-(U3-RTCOUT{slash}PB12-Pad24)") (class "Default")
      (node (ref "U3") (pin "24") (pinfunction "RTCOUT/PB12_24") (pintype "passive"))
    )
    (net (code "104") (name "unconnected-(U3-USBDM_PC6-Pad15)") (class "Default")
      (node (ref "U3") (pin "15") (pinfunction "USBDM_PC6_15") (pintype "passive"))
    )
    (net (code "105") (name "unconnected-(U3-USBDP_PC7-Pad16)") (class "Default")
      (node (ref "U3") (pin "16") (pinfunction "USBDP_PC7_16") (pintype "passive"))
    )
  )
)
